# TSC_Project.net
KiCad netlist of a schematic drawn in EAGLE
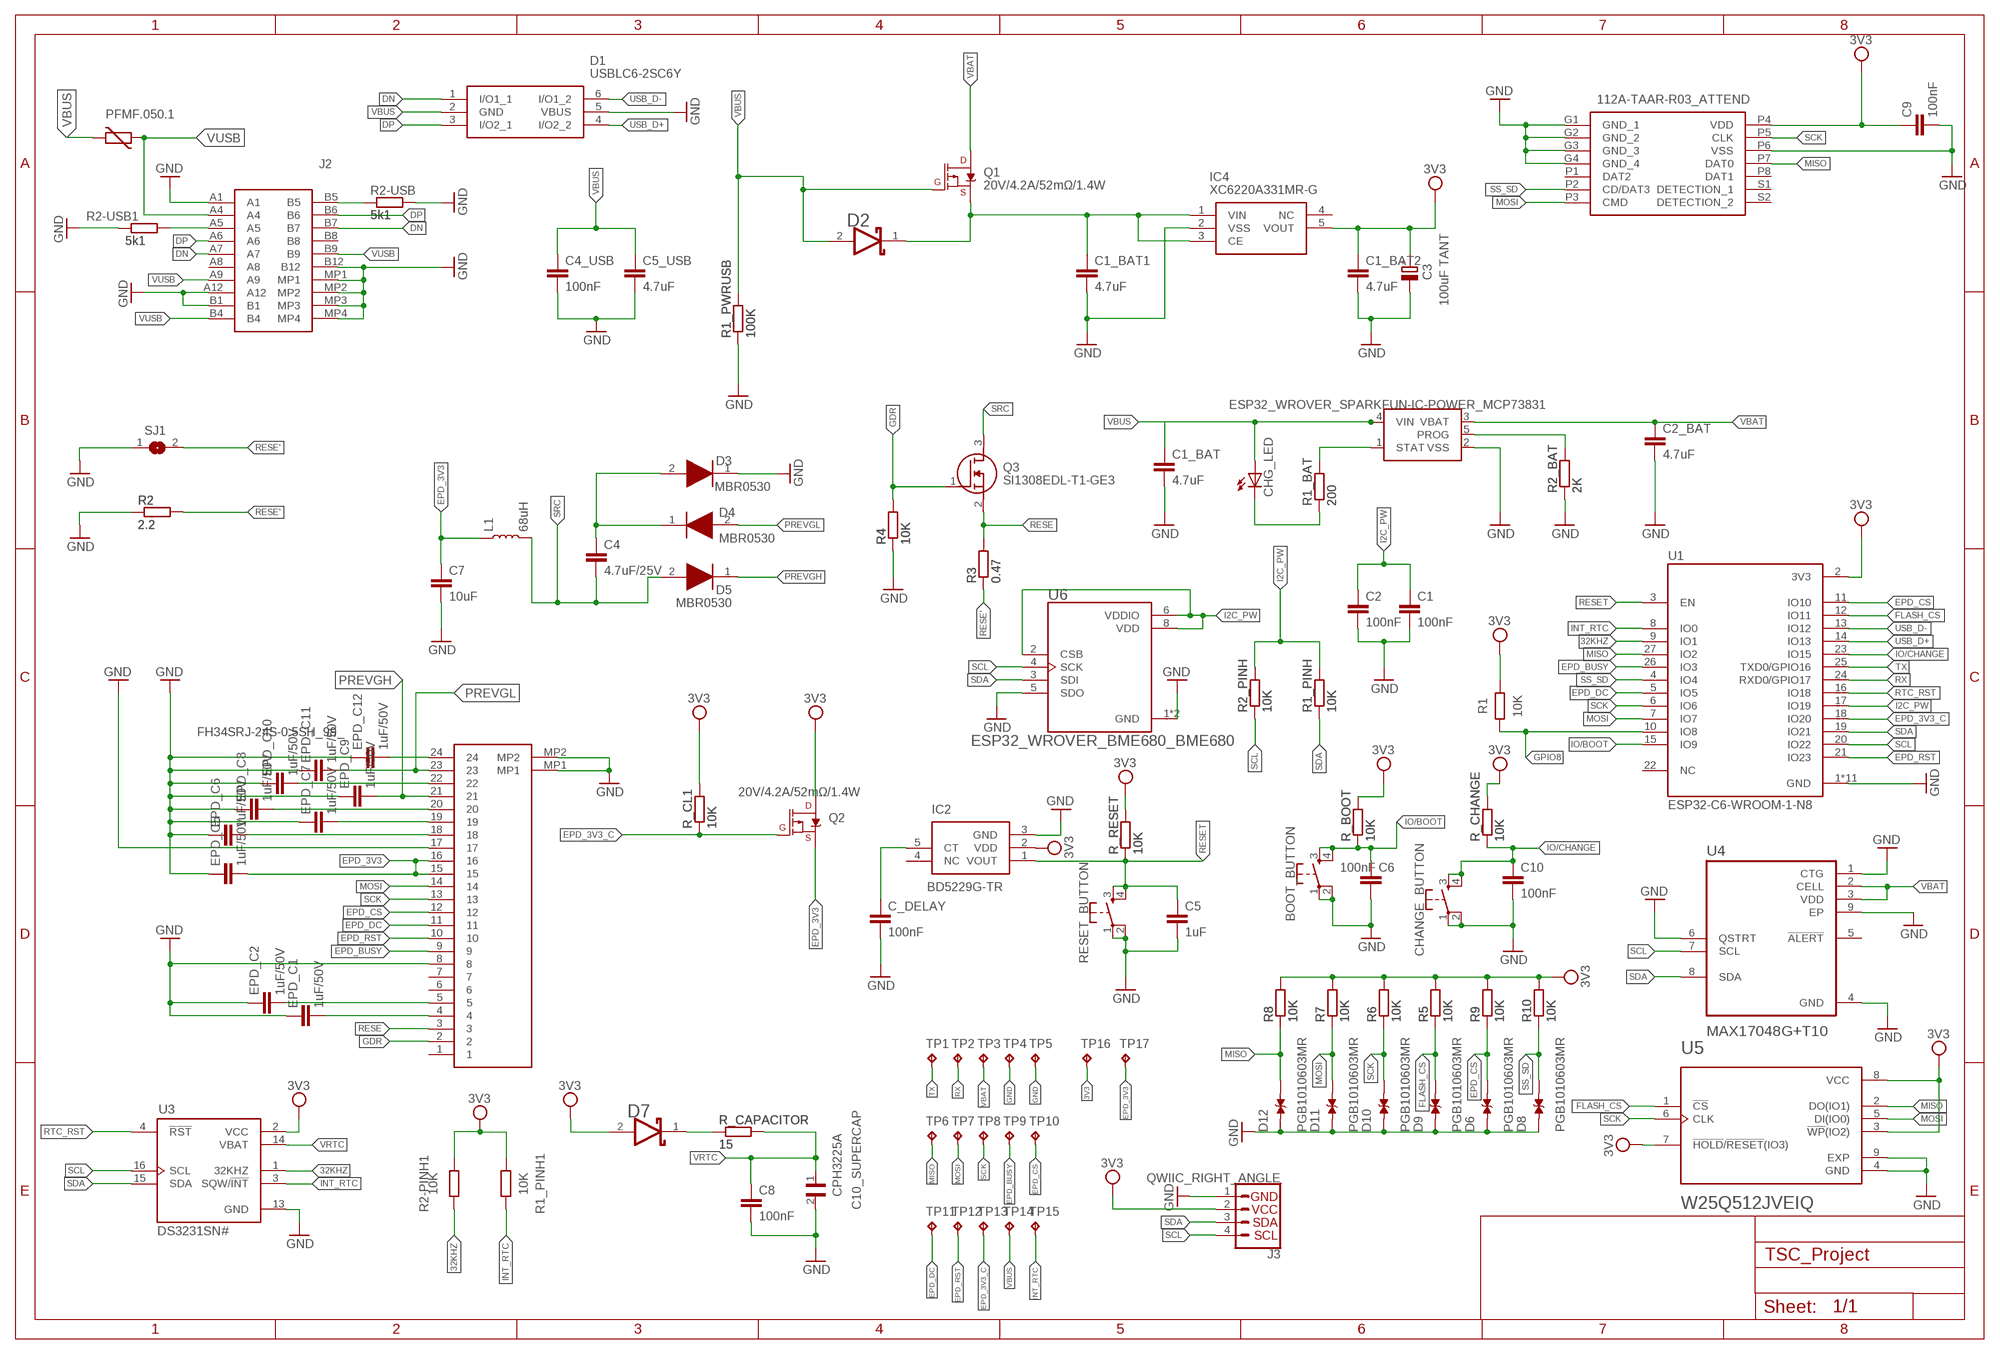
[diagram p0: schematic, sheet 1]

(export (version "E")
  (design (tool "Eeschema 10.0.6"))
  (components
    (comp (ref "BOOT_BUTTON")
      (value "BUTTON_CUSYOMV1")
      (footprint "eagle-import:MYBUTTON")
      (libsource (lib "eagle-import") (part "BUTTON_CUSYOMV1"))
    )
    (comp (ref "C1")
      (value "100nF")
      (footprint "eagle-import:ESP32_WROVER_EAGLE-LTSPICE_C0402")
      (libsource (lib "eagle-import") (part "ESP32_WROVER_EAGLE-LTSPICE_CC0402"))
    )
    (comp (ref "C1_BAT")
      (value "4.7uF")
      (footprint "eagle-import:ESP32_WROVER_EAGLE-LTSPICE_C0402")
      (libsource (lib "eagle-import") (part "ESP32_WROVER_EAGLE-LTSPICE_CC0402"))
    )
    (comp (ref "C1_BAT1")
      (value "4.7uF")
      (footprint "eagle-import:EAGLE-LTSPICE_C0402")
      (libsource (lib "eagle-import") (part "EAGLE-LTSPICE_CC0402"))
    )
    (comp (ref "C1_BAT2")
      (value "4.7uF")
      (footprint "eagle-import:EAGLE-LTSPICE_C0402")
      (libsource (lib "eagle-import") (part "EAGLE-LTSPICE_CC0402"))
    )
    (comp (ref "C2")
      (value "100nF")
      (footprint "eagle-import:ESP32_WROVER_EAGLE-LTSPICE_C0402")
      (libsource (lib "eagle-import") (part "ESP32_WROVER_EAGLE-LTSPICE_CC0402"))
    )
    (comp (ref "C2_BAT")
      (value "4.7uF")
      (footprint "eagle-import:ESP32_WROVER_EAGLE-LTSPICE_C0402")
      (libsource (lib "eagle-import") (part "ESP32_WROVER_EAGLE-LTSPICE_CC0402"))
    )
    (comp (ref "C3")
      (value "100uF TANT")
      (footprint "eagle-import:RCL_CT3528")
      (libsource (lib "eagle-import") (part "RCL_CPOL-EUCT3528"))
    )
    (comp (ref "C4")
      (value "4.7uF/25V")
      (footprint "eagle-import:ESP32_WROVER_EAGLE-LTSPICE_C0402")
      (libsource (lib "eagle-import") (part "ESP32_WROVER_EAGLE-LTSPICE_CC0402"))
    )
    (comp (ref "C4_USB")
      (value "100nF")
      (footprint "eagle-import:EAGLE-LTSPICE_C0402")
      (libsource (lib "eagle-import") (part "EAGLE-LTSPICE_CC0402"))
    )
    (comp (ref "C5")
      (value "1uF")
      (footprint "eagle-import:ESP32_WROVER_EAGLE-LTSPICE_C0402")
      (libsource (lib "eagle-import") (part "ESP32_WROVER_EAGLE-LTSPICE_CC0402"))
    )
    (comp (ref "C5_USB")
      (value "4.7uF")
      (footprint "eagle-import:EAGLE-LTSPICE_C0402")
      (libsource (lib "eagle-import") (part "EAGLE-LTSPICE_CC0402"))
    )
    (comp (ref "C6")
      (value "100nF")
      (footprint "eagle-import:ESP32_WROVER_EAGLE-LTSPICE_C0402")
      (libsource (lib "eagle-import") (part "ESP32_WROVER_EAGLE-LTSPICE_CC0402"))
    )
    (comp (ref "C7")
      (value "10uF")
      (footprint "eagle-import:ESP32_WROVER_EAGLE-LTSPICE_C0402")
      (libsource (lib "eagle-import") (part "ESP32_WROVER_EAGLE-LTSPICE_CC0402"))
    )
    (comp (ref "C8")
      (value "100nF")
      (footprint "eagle-import:ESP32_WROVER_EAGLE-LTSPICE_C0402")
      (libsource (lib "eagle-import") (part "ESP32_WROVER_EAGLE-LTSPICE_CC0402"))
    )
    (comp (ref "C9")
      (value "100nF")
      (footprint "eagle-import:ESP32_WROVER_EAGLE-LTSPICE_C0402")
      (libsource (lib "eagle-import") (part "ESP32_WROVER_EAGLE-LTSPICE_CC0402"))
    )
    (comp (ref "C10")
      (value "100nF")
      (footprint "eagle-import:ESP32_WROVER_EAGLE-LTSPICE_C0402")
      (libsource (lib "eagle-import") (part "ESP32_WROVER_EAGLE-LTSPICE_CC0402"))
    )
    (comp (ref "C10_SUPERCAP")
      (value "CPH3225A")
      (footprint "eagle-import:CAPCP3225X100N")
      (fields (field (name "MF") "Seiko Instruments"))
      (libsource (lib "eagle-import") (part "CPH3225A"))
    )
    (comp (ref "CHANGE_BUTTON")
      (value "BUTTON_CUSYOMV1")
      (footprint "eagle-import:MYBUTTON")
      (libsource (lib "eagle-import") (part "BUTTON_CUSYOMV1"))
    )
    (comp (ref "CHG_LED")
      (value "ADAFRUIT_LEDCHIP-LED0603")
      (footprint "eagle-import:ADAFRUIT_CHIP-LED0603")
      (libsource (lib "eagle-import") (part "ADAFRUIT_LEDCHIP-LED0603"))
    )
    (comp (ref "C_DELAY")
      (value "100nF")
      (footprint "eagle-import:EAGLE-LTSPICE_C0402")
      (libsource (lib "eagle-import") (part "EAGLE-LTSPICE_CC0402"))
    )
    (comp (ref "D1")
      (value "USBLC6-2SC6Y")
      (footprint "eagle-import:SOT95P280X145-6N")
      (fields (field (name "MF") "STMicroelectronics"))
      (libsource (lib "eagle-import") (part "USBLC6-2SC6Y"))
    )
    (comp (ref "D2")
      (value "ESP32_WROVER_AVX---SD0805S020S1R0_AVX_SD0805S020S1R0_0_0AVX_SD0805S020S1R0_0_0")
      (footprint "eagle-import:ESP32_WROVER_AVX---SD0805S020S1R0_AVX_SD0805S020S1R0_0")
      (fields
        (field (name "DIGIKEY_PART_NUMBER") "478-7800-1-ND")
        (field (name "MF") "AVX")
        (field (name "MOUSER_PART_NUMBER") "581-SD0805S020S1R0")
      )
      (libsource (lib "eagle-import") (part "ESP32_WROVER_AVX---SD0805S020S1R0_AVX_SD0805S020S1R0_0_0AVX_SD0805S020S1R0_0_0"))
    )
    (comp (ref "D3")
      (value "MBR0530")
      (footprint "eagle-import:SOD3716X135N")
      (fields (field (name "MF") "ON Semiconductor"))
      (libsource (lib "eagle-import") (part "MBR0530"))
    )
    (comp (ref "D4")
      (value "MBR0530")
      (footprint "eagle-import:SOD3716X135N")
      (fields (field (name "MF") "ON Semiconductor"))
      (libsource (lib "eagle-import") (part "MBR0530"))
    )
    (comp (ref "D5")
      (value "MBR0530")
      (footprint "eagle-import:SOD3716X135N")
      (fields (field (name "MF") "ON Semiconductor"))
      (libsource (lib "eagle-import") (part "MBR0530"))
    )
    (comp (ref "D6")
      (value "PGB1010603MR")
      (footprint "eagle-import:DIOC1608X36N")
      (fields (field (name "MF") "Littelfuse Inc."))
      (libsource (lib "eagle-import") (part "PGB1010603MR"))
    )
    (comp (ref "D7")
      (value "ESP32_WROVER_AVX---SD0805S020S1R0_AVX_SD0805S020S1R0_0_0AVX_SD0805S020S1R0_0_0")
      (footprint "eagle-import:ESP32_WROVER_AVX---SD0805S020S1R0_AVX_SD0805S020S1R0_0")
      (fields
        (field (name "DIGIKEY_PART_NUMBER") "478-7800-1-ND")
        (field (name "MF") "AVX")
        (field (name "MOUSER_PART_NUMBER") "581-SD0805S020S1R0")
      )
      (libsource (lib "eagle-import") (part "ESP32_WROVER_AVX---SD0805S020S1R0_AVX_SD0805S020S1R0_0_0AVX_SD0805S020S1R0_0_0"))
    )
    (comp (ref "D8")
      (value "PGB1010603MR")
      (footprint "eagle-import:DIOC1608X36N")
      (fields (field (name "MF") "Littelfuse Inc."))
      (libsource (lib "eagle-import") (part "PGB1010603MR"))
    )
    (comp (ref "D9")
      (value "PGB1010603MR")
      (footprint "eagle-import:DIOC1608X36N")
      (fields (field (name "MF") "Littelfuse Inc."))
      (libsource (lib "eagle-import") (part "PGB1010603MR"))
    )
    (comp (ref "D10")
      (value "PGB1010603MR")
      (footprint "eagle-import:DIOC1608X36N")
      (fields (field (name "MF") "Littelfuse Inc."))
      (libsource (lib "eagle-import") (part "PGB1010603MR"))
    )
    (comp (ref "D11")
      (value "PGB1010603MR")
      (footprint "eagle-import:DIOC1608X36N")
      (fields (field (name "MF") "Littelfuse Inc."))
      (libsource (lib "eagle-import") (part "PGB1010603MR"))
    )
    (comp (ref "D12")
      (value "PGB1010603MR")
      (footprint "eagle-import:DIOC1608X36N")
      (fields (field (name "MF") "Littelfuse Inc."))
      (libsource (lib "eagle-import") (part "PGB1010603MR"))
    )
    (comp (ref "EPD_C1")
      (value "1uF/50V")
      (footprint "eagle-import:ESP32_WROVER_EAGLE-LTSPICE_C0402")
      (libsource (lib "eagle-import") (part "ESP32_WROVER_EAGLE-LTSPICE_CC0402"))
    )
    (comp (ref "EPD_C2")
      (value "1uF/50V")
      (footprint "eagle-import:ESP32_WROVER_EAGLE-LTSPICE_C0402")
      (libsource (lib "eagle-import") (part "ESP32_WROVER_EAGLE-LTSPICE_CC0402"))
    )
    (comp (ref "EPD_C5")
      (value "1uF/50V")
      (footprint "eagle-import:ESP32_WROVER_EAGLE-LTSPICE_C0402")
      (libsource (lib "eagle-import") (part "ESP32_WROVER_EAGLE-LTSPICE_CC0402"))
    )
    (comp (ref "EPD_C6")
      (value "1uF/50V")
      (footprint "eagle-import:ESP32_WROVER_EAGLE-LTSPICE_C0402")
      (libsource (lib "eagle-import") (part "ESP32_WROVER_EAGLE-LTSPICE_CC0402"))
    )
    (comp (ref "EPD_C7")
      (value "1uF/50V")
      (footprint "eagle-import:ESP32_WROVER_EAGLE-LTSPICE_C0402")
      (libsource (lib "eagle-import") (part "ESP32_WROVER_EAGLE-LTSPICE_CC0402"))
    )
    (comp (ref "EPD_C8")
      (value "1uF/50V")
      (footprint "eagle-import:ESP32_WROVER_EAGLE-LTSPICE_C0402")
      (libsource (lib "eagle-import") (part "ESP32_WROVER_EAGLE-LTSPICE_CC0402"))
    )
    (comp (ref "EPD_C9")
      (value "1uF/50V")
      (footprint "eagle-import:ESP32_WROVER_EAGLE-LTSPICE_C0402")
      (libsource (lib "eagle-import") (part "ESP32_WROVER_EAGLE-LTSPICE_CC0402"))
    )
    (comp (ref "EPD_C10")
      (value "1uF/50V")
      (footprint "eagle-import:ESP32_WROVER_EAGLE-LTSPICE_C0402")
      (libsource (lib "eagle-import") (part "ESP32_WROVER_EAGLE-LTSPICE_CC0402"))
    )
    (comp (ref "EPD_C11")
      (value "1uF/50V")
      (footprint "eagle-import:ESP32_WROVER_EAGLE-LTSPICE_C0402")
      (libsource (lib "eagle-import") (part "ESP32_WROVER_EAGLE-LTSPICE_CC0402"))
    )
    (comp (ref "EPD_C12")
      (value "1uF/50V")
      (footprint "eagle-import:ESP32_WROVER_EAGLE-LTSPICE_C0402")
      (libsource (lib "eagle-import") (part "ESP32_WROVER_EAGLE-LTSPICE_CC0402"))
    )
    (comp (ref "IC2")
      (value "BD5229G-TR")
      (footprint "eagle-import:SOT95P280X125-5N")
      (fields (field (name "MOUSER_PART_NUMBER") "755-BD5229G-TR"))
      (libsource (lib "eagle-import") (part "BD5229G-TR"))
    )
    (comp (ref "IC4")
      (value "XC6220A331MR-G")
      (footprint "eagle-import:SOT95P280X120-5N")
      (fields (field (name "MOUSER_PART_NUMBER") "865-XC6220A331MR-G"))
      (libsource (lib "eagle-import") (part "XC6220A331MR-G"))
    )
    (comp (ref "J1")
      (value "FH34SRJ-24S-0.5SH_99_")
      (footprint "eagle-import:FH34SRJ24S05SH99")
      (fields
        (field (name "MANUFACTURER_PART_NUMBER") "FH34SRJ-24S-0.5SH(99)")
        (field (name "MOUSER_PART_NUMBER") "798-FH34SRJ24S05SH99")
      )
      (libsource (lib "eagle-import") (part "FH34SRJ-24S-0.5SH_99_"))
    )
    (comp (ref "J2")
      (value "SAMACSYS_PARTS_USB4110-GF-A")
      (footprint "eagle-import:SAMACSYS_PARTS_USB4110GFA")
      (fields
        (field (name "MANUFACTURER_PART_NUMBER") "USB4110-GF-A")
        (field (name "MOUSER_PART_NUMBER") "640-USB4110-GF-A")
      )
      (libsource (lib "eagle-import") (part "SAMACSYS_PARTS_USB4110-GF-A"))
    )
    (comp (ref "J3")
      (value "QWIIC_RIGHT_ANGLE")
      (footprint "eagle-import:JST04_1MM_RA")
      (libsource (lib "eagle-import") (part "QWIIC_CONNECTORJS-1MM"))
    )
    (comp (ref "J4")
      (value "112A-TAAR-R03_ATTEND")
      (footprint "eagle-import:112ATAARR03ATTEND")
      (fields (field (name "MANUFACTURER_PART_NUMBER") "112A-TAAR-R03 ATTEND"))
      (libsource (lib "eagle-import") (part "112A-TAAR-R03_ATTEND"))
    )
    (comp (ref "L1")
      (value "68uH")
      (footprint "eagle-import:CR75")
      (libsource (lib "eagle-import") (part "INDUCTOR-CR75-68UH"))
    )
    (comp (ref "PFMF.050.1")
      (value "ESP32C6_VARISTORCN1812")
      (footprint "eagle-import:ESP32C6_VARISTOR_CT_CN1812")
      (libsource (lib "eagle-import") (part "ESP32C6_VARISTORCN1812"))
    )
    (comp (ref "Q1")
      (value "20V/4.2A/52mΩ/1.4W")
      (footprint "eagle-import:ESP32_WROVER_SPARKFUN-DISCRETESEMI_SOT23-3")
      (libsource (lib "eagle-import") (part "ESP32_WROVER_SPARKFUN-DISCRETESEMI_MOSFET_PCH-DMG2305UX-7"))
    )
    (comp (ref "Q2")
      (value "20V/4.2A/52mΩ/1.4W")
      (footprint "eagle-import:ESP32_WROVER_SPARKFUN-DISCRETESEMI_SOT23-3")
      (libsource (lib "eagle-import") (part "ESP32_WROVER_SPARKFUN-DISCRETESEMI_MOSFET_PCH-DMG2305UX-7"))
    )
    (comp (ref "Q3")
      (value "SI1308EDL-T1-GE3")
      (footprint "eagle-import:SOT65P210X110-3N")
      (fields (field (name "MF") "Vishay Siliconix"))
      (libsource (lib "eagle-import") (part "SI1308EDL-T1-GE3"))
    )
    (comp (ref "R1")
      (value "10K")
      (footprint "eagle-import:ESP32_WROVER_EAGLE-LTSPICE_R0402")
      (libsource (lib "eagle-import") (part "ESP32_WROVER_EAGLE-LTSPICE_RR0402"))
    )
    (comp (ref "R1_BAT")
      (value "200")
      (footprint "eagle-import:ESP32_WROVER_EAGLE-LTSPICE_R0402")
      (libsource (lib "eagle-import") (part "ESP32_WROVER_EAGLE-LTSPICE_RR0402"))
    )
    (comp (ref "R1_PINH")
      (value "10K")
      (footprint "eagle-import:ESP32_WROVER_EAGLE-LTSPICE_R0402")
      (libsource (lib "eagle-import") (part "ESP32_WROVER_EAGLE-LTSPICE_RR0402"))
    )
    (comp (ref "R1_PINH1")
      (value "10K")
      (footprint "eagle-import:ESP32_WROVER_EAGLE-LTSPICE_R0402")
      (libsource (lib "eagle-import") (part "ESP32_WROVER_EAGLE-LTSPICE_RR0402"))
    )
    (comp (ref "R1_PWRUSB")
      (value "100K")
      (footprint "eagle-import:ESP32_WROVER_EAGLE-LTSPICE_R0402")
      (libsource (lib "eagle-import") (part "ESP32_WROVER_EAGLE-LTSPICE_RR0402"))
    )
    (comp (ref "R2")
      (value "2.2")
      (footprint "eagle-import:ESP32_WROVER_EAGLE-LTSPICE_R0402")
      (libsource (lib "eagle-import") (part "ESP32_WROVER_EAGLE-LTSPICE_RR0402"))
    )
    (comp (ref "R2-PINH1")
      (value "10K")
      (footprint "eagle-import:ESP32_WROVER_EAGLE-LTSPICE_R0402")
      (libsource (lib "eagle-import") (part "ESP32_WROVER_EAGLE-LTSPICE_RR0402"))
    )
    (comp (ref "R2-USB")
      (value "5k1")
      (footprint "eagle-import:ESP32_WROVER_EAGLE-LTSPICE_R0402")
      (libsource (lib "eagle-import") (part "ESP32_WROVER_EAGLE-LTSPICE_RR0402"))
    )
    (comp (ref "R2-USB1")
      (value "5k1")
      (footprint "eagle-import:ESP32_WROVER_EAGLE-LTSPICE_R0402")
      (libsource (lib "eagle-import") (part "ESP32_WROVER_EAGLE-LTSPICE_RR0402"))
    )
    (comp (ref "R2_BAT")
      (value "2K")
      (footprint "eagle-import:ESP32_WROVER_EAGLE-LTSPICE_R0402")
      (libsource (lib "eagle-import") (part "ESP32_WROVER_EAGLE-LTSPICE_RR0402"))
    )
    (comp (ref "R2_PINH")
      (value "10K")
      (footprint "eagle-import:ESP32_WROVER_EAGLE-LTSPICE_R0402")
      (libsource (lib "eagle-import") (part "ESP32_WROVER_EAGLE-LTSPICE_RR0402"))
    )
    (comp (ref "R3")
      (value "0.47")
      (footprint "eagle-import:ESP32_WROVER_EAGLE-LTSPICE_R0402")
      (libsource (lib "eagle-import") (part "ESP32_WROVER_EAGLE-LTSPICE_RR0402"))
    )
    (comp (ref "R4")
      (value "10K")
      (footprint "eagle-import:ESP32_WROVER_EAGLE-LTSPICE_R0402")
      (libsource (lib "eagle-import") (part "ESP32_WROVER_EAGLE-LTSPICE_RR0402"))
    )
    (comp (ref "R5")
      (value "10K")
      (footprint "eagle-import:ESP32_WROVER_EAGLE-LTSPICE_R0402")
      (libsource (lib "eagle-import") (part "ESP32_WROVER_EAGLE-LTSPICE_RR0402"))
    )
    (comp (ref "R6")
      (value "10K")
      (footprint "eagle-import:ESP32_WROVER_EAGLE-LTSPICE_R0402")
      (libsource (lib "eagle-import") (part "ESP32_WROVER_EAGLE-LTSPICE_RR0402"))
    )
    (comp (ref "R7")
      (value "10K")
      (footprint "eagle-import:ESP32_WROVER_EAGLE-LTSPICE_R0402")
      (libsource (lib "eagle-import") (part "ESP32_WROVER_EAGLE-LTSPICE_RR0402"))
    )
    (comp (ref "R8")
      (value "10K")
      (footprint "eagle-import:ESP32_WROVER_EAGLE-LTSPICE_R0402")
      (libsource (lib "eagle-import") (part "ESP32_WROVER_EAGLE-LTSPICE_RR0402"))
    )
    (comp (ref "R9")
      (value "10K")
      (footprint "eagle-import:ESP32_WROVER_EAGLE-LTSPICE_R0402")
      (libsource (lib "eagle-import") (part "ESP32_WROVER_EAGLE-LTSPICE_RR0402"))
    )
    (comp (ref "R10")
      (value "10K")
      (footprint "eagle-import:ESP32_WROVER_EAGLE-LTSPICE_R0402")
      (libsource (lib "eagle-import") (part "ESP32_WROVER_EAGLE-LTSPICE_RR0402"))
    )
    (comp (ref "RESET_BUTTON")
      (value "BUTTON_CUSYOMV1")
      (footprint "eagle-import:MYBUTTON")
      (libsource (lib "eagle-import") (part "BUTTON_CUSYOMV1"))
    )
    (comp (ref "R_BOOT")
      (value "10K")
      (footprint "eagle-import:ESP32_WROVER_EAGLE-LTSPICE_R0402")
      (libsource (lib "eagle-import") (part "ESP32_WROVER_EAGLE-LTSPICE_RR0402"))
    )
    (comp (ref "R_CAPACITOR")
      (value "15")
      (footprint "eagle-import:ESP32_WROVER_EAGLE-LTSPICE_R0402")
      (libsource (lib "eagle-import") (part "ESP32_WROVER_EAGLE-LTSPICE_RR0402"))
    )
    (comp (ref "R_CHANGE")
      (value "10K")
      (footprint "eagle-import:ESP32_WROVER_EAGLE-LTSPICE_R0402")
      (libsource (lib "eagle-import") (part "ESP32_WROVER_EAGLE-LTSPICE_RR0402"))
    )
    (comp (ref "R_CL1")
      (value "10K")
      (footprint "eagle-import:ESP32_WROVER_EAGLE-LTSPICE_R0402")
      (libsource (lib "eagle-import") (part "ESP32_WROVER_EAGLE-LTSPICE_RR0402"))
    )
    (comp (ref "R_RESET")
      (value "10K")
      (footprint "eagle-import:ESP32_WROVER_EAGLE-LTSPICE_R0402")
      (libsource (lib "eagle-import") (part "ESP32_WROVER_EAGLE-LTSPICE_RR0402"))
    )
    (comp (ref "SJ1") (value "SJ") (footprint "eagle-import:SJ") (libsource (lib "eagle-import") (part "SJ")))
    (comp (ref "TP1")
      (value "TPTP20R")
      (footprint "eagle-import:TP20R")
      (libsource (lib "eagle-import") (part "TPTP20R"))
    )
    (comp (ref "TP2")
      (value "TPTP20R")
      (footprint "eagle-import:TP20R")
      (libsource (lib "eagle-import") (part "TPTP20R"))
    )
    (comp (ref "TP3")
      (value "TPTP20R")
      (footprint "eagle-import:TP20R")
      (libsource (lib "eagle-import") (part "TPTP20R"))
    )
    (comp (ref "TP4")
      (value "TPTP20R")
      (footprint "eagle-import:TP20R")
      (libsource (lib "eagle-import") (part "TPTP20R"))
    )
    (comp (ref "TP5")
      (value "TPTP20R")
      (footprint "eagle-import:TP20R")
      (libsource (lib "eagle-import") (part "TPTP20R"))
    )
    (comp (ref "TP6")
      (value "TPTP20R")
      (footprint "eagle-import:TP20R")
      (libsource (lib "eagle-import") (part "TPTP20R"))
    )
    (comp (ref "TP7")
      (value "TPTP20R")
      (footprint "eagle-import:TP20R")
      (libsource (lib "eagle-import") (part "TPTP20R"))
    )
    (comp (ref "TP8")
      (value "TPTP20R")
      (footprint "eagle-import:TP20R")
      (libsource (lib "eagle-import") (part "TPTP20R"))
    )
    (comp (ref "TP9")
      (value "TPTP20R")
      (footprint "eagle-import:TP20R")
      (libsource (lib "eagle-import") (part "TPTP20R"))
    )
    (comp (ref "TP10")
      (value "TPTP20R")
      (footprint "eagle-import:TP20R")
      (libsource (lib "eagle-import") (part "TPTP20R"))
    )
    (comp (ref "TP11")
      (value "TPTP20R")
      (footprint "eagle-import:TP20R")
      (libsource (lib "eagle-import") (part "TPTP20R"))
    )
    (comp (ref "TP12")
      (value "TPTP20R")
      (footprint "eagle-import:TP20R")
      (libsource (lib "eagle-import") (part "TPTP20R"))
    )
    (comp (ref "TP13")
      (value "TPTP20R")
      (footprint "eagle-import:TP20R")
      (libsource (lib "eagle-import") (part "TPTP20R"))
    )
    (comp (ref "TP14")
      (value "TPTP20R")
      (footprint "eagle-import:TP20R")
      (libsource (lib "eagle-import") (part "TPTP20R"))
    )
    (comp (ref "TP15")
      (value "TPTP20R")
      (footprint "eagle-import:TP20R")
      (libsource (lib "eagle-import") (part "TPTP20R"))
    )
    (comp (ref "TP16")
      (value "TPTP20R")
      (footprint "eagle-import:TP20R")
      (libsource (lib "eagle-import") (part "TPTP20R"))
    )
    (comp (ref "TP17")
      (value "TPTP20R")
      (footprint "eagle-import:TP20R")
      (libsource (lib "eagle-import") (part "TPTP20R"))
    )
    (comp (ref "U1")
      (value "ESP32-C6-WROOM-1-N8")
      (footprint "eagle-import:XCVR_ESP32-C6-WROOM-1-N8")
      (fields (field (name "MF") "Espressif Systems"))
      (libsource (lib "eagle-import") (part "ESP32-C6-WROOM-1-N8"))
    )
    (comp (ref "U2")
      (value "ESP32_WROVER_SPARKFUN-IC-POWER_MCP73831")
      (footprint "eagle-import:ESP32_WROVER_SPARKFUN-IC-POWER_SOT23-5")
      (libsource (lib "eagle-import") (part "ESP32_WROVER_SPARKFUN-IC-POWER_MCP73831"))
    )
    (comp (ref "U3")
      (value "DS3231SN#")
      (footprint "eagle-import:SOIC127P1032X265-16N")
      (fields (field (name "MF") "Analog Devices"))
      (libsource (lib "eagle-import") (part "DS3231SN#"))
    )
    (comp (ref "U4")
      (value "MAX17048G+T10")
      (footprint "eagle-import:SON50P200X200X80-9N")
      (fields (field (name "MF") "Analog Devices"))
      (libsource (lib "eagle-import") (part "MAX17048G+T10"))
    )
    (comp (ref "U5")
      (value "W25Q512JVEIQ")
      (footprint "eagle-import:SON127P600X800X80-9N")
      (fields (field (name "MF") "Winbond Electronics"))
      (libsource (lib "eagle-import") (part "W25Q512JVEIQ"))
    )
    (comp (ref "U6")
      (value "ESP32_WROVER_BME680_BME680")
      (footprint "eagle-import:ESP32_WROVER_BME680_PSON80P300X300X100-8N")
      (fields (field (name "MF") "Bosch Sensortec") (field (name "MP") "BME680"))
      (libsource (lib "eagle-import") (part "ESP32_WROVER_BME680_BME680"))
    )
  )
  (nets
    (net (code "1") (name "3V3") (class "Default")
      (node (ref "C1_BAT2") (pin "1") (pinfunction "1_1") (pintype "passive"))
      (node (ref "C3") (pin "+") (pinfunction "+_+") (pintype "passive"))
      (node (ref "C9") (pin "1") (pinfunction "1_1") (pintype "passive"))
      (node (ref "D7") (pin "2") (pinfunction "ANODE_2") (pintype "bidirectional"))
      (node (ref "IC2") (pin "2") (pinfunction "VDD_2") (pintype "bidirectional"))
      (node (ref "IC4") (pin "5") (pinfunction "VOUT_5") (pintype "bidirectional"))
      (node (ref "J3") (pin "2") (pinfunction "2_2") (pintype "power_in"))
      (node (ref "J4") (pin "P4") (pinfunction "VDD_P4") (pintype "bidirectional"))
      (node (ref "Q2") (pin "3") (pinfunction "D_3") (pintype "bidirectional"))
      (node (ref "R1") (pin "2") (pinfunction "2_2") (pintype "passive"))
      (node (ref "R10") (pin "2") (pinfunction "2_2") (pintype "passive"))
      (node (ref "R1_PINH1") (pin "2") (pinfunction "2_2") (pintype "passive"))
      (node (ref "R2-PINH1") (pin "2") (pinfunction "2_2") (pintype "passive"))
      (node (ref "R5") (pin "2") (pinfunction "2_2") (pintype "passive"))
      (node (ref "R6") (pin "2") (pinfunction "2_2") (pintype "passive"))
      (node (ref "R7") (pin "2") (pinfunction "2_2") (pintype "passive"))
      (node (ref "R8") (pin "2") (pinfunction "2_2") (pintype "passive"))
      (node (ref "R9") (pin "2") (pinfunction "2_2") (pintype "passive"))
      (node (ref "R_BOOT") (pin "2") (pinfunction "2_2") (pintype "passive"))
      (node (ref "R_CHANGE") (pin "2") (pinfunction "2_2") (pintype "passive"))
      (node (ref "R_CL1") (pin "2") (pinfunction "2_2") (pintype "passive"))
      (node (ref "R_RESET") (pin "2") (pinfunction "2_2") (pintype "passive"))
      (node (ref "TP16") (pin "TP") (pinfunction "TP_TP") (pintype "input"))
      (node (ref "U1") (pin "2") (pinfunction "3V3_2") (pintype "power_in"))
      (node (ref "U3") (pin "2") (pinfunction "VCC_2") (pintype "power_in"))
      (node (ref "U5") (pin "3") (pinfunction "~{WP}(IO2)_3") (pintype "bidirectional"))
      (node (ref "U5") (pin "7") (pinfunction "~{HOLD}/~{RESET}(IO3)_7") (pintype "bidirectional"))
      (node (ref "U5") (pin "8") (pinfunction "VCC_8") (pintype "power_in"))
    )
    (net (code "2") (name "32KHZ") (class "Default")
      (node (ref "R2-PINH1") (pin "1") (pinfunction "1_1") (pintype "passive"))
      (node (ref "U1") (pin "9") (pinfunction "IO1_9") (pintype "bidirectional"))
      (node (ref "U3") (pin "1") (pinfunction "32KHZ_1") (pintype "output"))
    )
    (net (code "3") (name "DN") (class "Default")
      (node (ref "D1") (pin "1") (pinfunction "I/O1_1_1") (pintype "bidirectional"))
      (node (ref "J2") (pin "A7") (pinfunction "A7_A7") (pintype "bidirectional"))
      (node (ref "J2") (pin "B7") (pinfunction "B7_B7") (pintype "bidirectional"))
    )
    (net (code "4") (name "DP") (class "Default")
      (node (ref "D1") (pin "3") (pinfunction "I/O2_1_3") (pintype "bidirectional"))
      (node (ref "J2") (pin "A6") (pinfunction "A6_A6") (pintype "bidirectional"))
      (node (ref "J2") (pin "B6") (pinfunction "B6_B6") (pintype "bidirectional"))
    )
    (net (code "5") (name "EPD_3V3") (class "Default")
      (node (ref "C7") (pin "1") (pinfunction "1_1") (pintype "passive"))
      (node (ref "EPD_C5") (pin "2") (pinfunction "2_2") (pintype "passive"))
      (node (ref "J1") (pin "15") (pinfunction "15_15") (pintype "bidirectional"))
      (node (ref "J1") (pin "16") (pinfunction "16_16") (pintype "bidirectional"))
      (node (ref "L1") (pin "P$1") (pinfunction "1_P$1") (pintype "passive"))
      (node (ref "Q2") (pin "2") (pinfunction "S_2") (pintype "bidirectional"))
      (node (ref "TP17") (pin "TP") (pinfunction "TP_TP") (pintype "input"))
    )
    (net (code "6") (name "EPD_3V3_C") (class "Default")
      (node (ref "Q2") (pin "1") (pinfunction "G_1") (pintype "bidirectional"))
      (node (ref "R_CL1") (pin "1") (pinfunction "1_1") (pintype "passive"))
      (node (ref "TP13") (pin "TP") (pinfunction "TP_TP") (pintype "input"))
      (node (ref "U1") (pin "18") (pinfunction "IO20_18") (pintype "bidirectional"))
    )
    (net (code "7") (name "EPD_BUSY") (class "Default")
      (node (ref "J1") (pin "9") (pinfunction "9_9") (pintype "bidirectional"))
      (node (ref "TP9") (pin "TP") (pinfunction "TP_TP") (pintype "input"))
      (node (ref "U1") (pin "26") (pinfunction "IO3_26") (pintype "bidirectional"))
    )
    (net (code "8") (name "EPD_CS") (class "Default")
      (node (ref "D6") (pin "2") (pinfunction "2_2") (pintype "passive"))
      (node (ref "J1") (pin "12") (pinfunction "12_12") (pintype "bidirectional"))
      (node (ref "R9") (pin "1") (pinfunction "1_1") (pintype "passive"))
      (node (ref "TP10") (pin "TP") (pinfunction "TP_TP") (pintype "input"))
      (node (ref "U1") (pin "11") (pinfunction "IO10_11") (pintype "bidirectional"))
    )
    (net (code "9") (name "EPD_DC") (class "Default")
      (node (ref "J1") (pin "11") (pinfunction "11_11") (pintype "bidirectional"))
      (node (ref "TP11") (pin "TP") (pinfunction "TP_TP") (pintype "input"))
      (node (ref "U1") (pin "5") (pinfunction "IO5_5") (pintype "bidirectional"))
    )
    (net (code "10") (name "EPD_RST") (class "Default")
      (node (ref "J1") (pin "10") (pinfunction "10_10") (pintype "bidirectional"))
      (node (ref "TP12") (pin "TP") (pinfunction "TP_TP") (pintype "input"))
      (node (ref "U1") (pin "21") (pinfunction "IO23_21") (pintype "bidirectional"))
    )
    (net (code "11") (name "FLASH_CS") (class "Default")
      (node (ref "D9") (pin "2") (pinfunction "2_2") (pintype "passive"))
      (node (ref "R5") (pin "1") (pinfunction "1_1") (pintype "passive"))
      (node (ref "U1") (pin "12") (pinfunction "IO11_12") (pintype "bidirectional"))
      (node (ref "U5") (pin "1") (pinfunction "~{CS}_1") (pintype "input"))
    )
    (net (code "12") (name "GDR") (class "Default")
      (node (ref "J1") (pin "2") (pinfunction "2_2") (pintype "bidirectional"))
      (node (ref "Q3") (pin "1") (pinfunction "G_1") (pintype "bidirectional"))
      (node (ref "R4") (pin "2") (pinfunction "2_2") (pintype "passive"))
    )
    (net (code "13") (name "GND") (class "Default")
      (node (ref "BOOT_BUTTON") (pin "1") (pinfunction "1_1") (pintype "passive"))
      (node (ref "BOOT_BUTTON") (pin "2") (pinfunction "2_2") (pintype "passive"))
      (node (ref "C1") (pin "2") (pinfunction "2_2") (pintype "passive"))
      (node (ref "C10") (pin "2") (pinfunction "2_2") (pintype "passive"))
      (node (ref "C10_SUPERCAP") (pin "2") (pinfunction "2_2") (pintype "passive"))
      (node (ref "C1_BAT") (pin "2") (pinfunction "2_2") (pintype "passive"))
      (node (ref "C1_BAT1") (pin "2") (pinfunction "2_2") (pintype "passive"))
      (node (ref "C1_BAT2") (pin "2") (pinfunction "2_2") (pintype "passive"))
      (node (ref "C2") (pin "2") (pinfunction "2_2") (pintype "passive"))
      (node (ref "C2_BAT") (pin "2") (pinfunction "2_2") (pintype "passive"))
      (node (ref "C3") (pin "-") (pinfunction "-_-") (pintype "passive"))
      (node (ref "C4_USB") (pin "2") (pinfunction "2_2") (pintype "passive"))
      (node (ref "C5") (pin "2") (pinfunction "2_2") (pintype "passive"))
      (node (ref "C5_USB") (pin "2") (pinfunction "2_2") (pintype "passive"))
      (node (ref "C6") (pin "2") (pinfunction "2_2") (pintype "passive"))
      (node (ref "C7") (pin "2") (pinfunction "2_2") (pintype "passive"))
      (node (ref "C8") (pin "2") (pinfunction "2_2") (pintype "passive"))
      (node (ref "C9") (pin "2") (pinfunction "2_2") (pintype "passive"))
      (node (ref "CHANGE_BUTTON") (pin "1") (pinfunction "1_1") (pintype "passive"))
      (node (ref "CHANGE_BUTTON") (pin "2") (pinfunction "2_2") (pintype "passive"))
      (node (ref "C_DELAY") (pin "2") (pinfunction "2_2") (pintype "passive"))
      (node (ref "D1") (pin "5") (pinfunction "VBUS_5") (pintype "bidirectional"))
      (node (ref "D10") (pin "1") (pinfunction "1_1") (pintype "passive"))
      (node (ref "D11") (pin "1") (pinfunction "1_1") (pintype "passive"))
      (node (ref "D12") (pin "1") (pinfunction "1_1") (pintype "passive"))
      (node (ref "D3") (pin "1") (pinfunction "K_1") (pintype "bidirectional"))
      (node (ref "D6") (pin "1") (pinfunction "1_1") (pintype "passive"))
      (node (ref "D8") (pin "1") (pinfunction "1_1") (pintype "passive"))
      (node (ref "D9") (pin "1") (pinfunction "1_1") (pintype "passive"))
      (node (ref "EPD_C1") (pin "1") (pinfunction "1_1") (pintype "passive"))
      (node (ref "EPD_C10") (pin "1") (pinfunction "1_1") (pintype "passive"))
      (node (ref "EPD_C11") (pin "1") (pinfunction "1_1") (pintype "passive"))
      (node (ref "EPD_C12") (pin "1") (pinfunction "1_1") (pintype "passive"))
      (node (ref "EPD_C2") (pin "1") (pinfunction "1_1") (pintype "passive"))
      (node (ref "EPD_C5") (pin "1") (pinfunction "1_1") (pintype "passive"))
      (node (ref "EPD_C6") (pin "1") (pinfunction "1_1") (pintype "passive"))
      (node (ref "EPD_C7") (pin "1") (pinfunction "1_1") (pintype "passive"))
      (node (ref "EPD_C8") (pin "1") (pinfunction "1_1") (pintype "passive"))
      (node (ref "EPD_C9") (pin "1") (pinfunction "1_1") (pintype "passive"))
      (node (ref "IC2") (pin "3") (pinfunction "GND_3") (pintype "bidirectional"))
      (node (ref "IC4") (pin "2") (pinfunction "VSS_2") (pintype "bidirectional"))
      (node (ref "J1") (pin "17") (pinfunction "17_17") (pintype "bidirectional"))
      (node (ref "J1") (pin "8") (pinfunction "8_8") (pintype "bidirectional"))
      (node (ref "J1") (pin "MP1") (pinfunction "MP1_MP1") (pintype "bidirectional"))
      (node (ref "J1") (pin "MP2") (pinfunction "MP2_MP2") (pintype "bidirectional"))
      (node (ref "J2") (pin "A1") (pinfunction "A1_A1") (pintype "bidirectional"))
      (node (ref "J2") (pin "A12") (pinfunction "A12_A12") (pintype "bidirectional"))
      (node (ref "J2") (pin "B1") (pinfunction "B1_B1") (pintype "bidirectional"))
      (node (ref "J2") (pin "B12") (pinfunction "B12_B12") (pintype "bidirectional"))
      (node (ref "J2") (pin "MP1") (pinfunction "MP1_MP1") (pintype "bidirectional"))
      (node (ref "J2") (pin "MP2") (pinfunction "MP2_MP2") (pintype "bidirectional"))
      (node (ref "J2") (pin "MP3") (pinfunction "MP3_MP3") (pintype "bidirectional"))
      (node (ref "J2") (pin "MP4") (pinfunction "MP4_MP4") (pintype "bidirectional"))
      (node (ref "J3") (pin "1") (pinfunction "1_1") (pintype "power_in"))
      (node (ref "J4") (pin "G1") (pinfunction "GND_1_G1") (pintype "bidirectional"))
      (node (ref "J4") (pin "G2") (pinfunction "GND_2_G2") (pintype "bidirectional"))
      (node (ref "J4") (pin "G3") (pinfunction "GND_3_G3") (pintype "bidirectional"))
      (node (ref "J4") (pin "G4") (pinfunction "GND_4_G4") (pintype "bidirectional"))
      (node (ref "J4") (pin "P6") (pinfunction "VSS_P6") (pintype "bidirectional"))
      (node (ref "R1_PWRUSB") (pin "1") (pinfunction "1_1") (pintype "passive"))
      (node (ref "R2") (pin "1") (pinfunction "1_1") (pintype "passive"))
      (node (ref "R2-USB") (pin "2") (pinfunction "2_2") (pintype "passive"))
      (node (ref "R2-USB1") (pin "1") (pinfunction "1_1") (pintype "passive"))
      (node (ref "R2_BAT") (pin "1") (pinfunction "1_1") (pintype "passive"))
      (node (ref "R4") (pin "1") (pinfunction "1_1") (pintype "passive"))
      (node (ref "RESET_BUTTON") (pin "1") (pinfunction "1_1") (pintype "passive"))
      (node (ref "RESET_BUTTON") (pin "2") (pinfunction "2_2") (pintype "passive"))
      (node (ref "SJ1") (pin "1") (pinfunction "1_1") (pintype "passive"))
      (node (ref "TP4") (pin "TP") (pinfunction "TP_TP") (pintype "input"))
      (node (ref "TP5") (pin "TP") (pinfunction "TP_TP") (pintype "input"))
      (node (ref "U1") (pin "1") (pinfunction "GND_1") (pintype "power_in"))
      (node (ref "U1") (pin "28") (pinfunction "GND_28") (pintype "power_in"))
      (node (ref "U1") (pin "29_1") (pinfunction "GND_29_1") (pintype "power_in"))
      (node (ref "U1") (pin "29_2") (pinfunction "GND_29_2") (pintype "power_in"))
      (node (ref "U1") (pin "29_3") (pinfunction "GND_29_3") (pintype "power_in"))
      (node (ref "U1") (pin "29_4") (pinfunction "GND_29_4") (pintype "power_in"))
      (node (ref "U1") (pin "29_5") (pinfunction "GND_29_5") (pintype "power_in"))
      (node (ref "U1") (pin "29_6") (pinfunction "GND_29_6") (pintype "power_in"))
      (node (ref "U1") (pin "29_7") (pinfunction "GND_29_7") (pintype "power_in"))
      (node (ref "U1") (pin "29_8") (pinfunction "GND_29_8") (pintype "power_in"))
      (node (ref "U1") (pin "29_9") (pinfunction "GND_29_9") (pintype "power_in"))
      (node (ref "U2") (pin "2") (pinfunction "VSS_2") (pintype "power_in"))
      (node (ref "U3") (pin "13") (pinfunction "GND_13") (pintype "power_in"))
      (node (ref "U4") (pin "1") (pinfunction "CTG_1") (pintype "power_in"))
      (node (ref "U4") (pin "4") (pinfunction "GND_4") (pintype "power_in"))
      (node (ref "U4") (pin "6") (pinfunction "QSTRT_6") (pintype "input"))
      (node (ref "U4") (pin "9") (pinfunction "EP_9") (pintype "power_in"))
      (node (ref "U5") (pin "4") (pinfunction "GND_4") (pintype "power_in"))
      (node (ref "U5") (pin "9") (pinfunction "EXP_9") (pintype "passive"))
      (node (ref "U6") (pin "1") (pinfunction "GND_1") (pintype "power_in"))
      (node (ref "U6") (pin "5") (pinfunction "SDO_5") (pintype "bidirectional"))
      (node (ref "U6") (pin "7") (pinfunction "GND_7") (pintype "power_in"))
    )
    (net (code "14") (name "GPIO8") (class "Default")
      (node (ref "R1") (pin "1") (pinfunction "1_1") (pintype "passive"))
      (node (ref "U1") (pin "10") (pinfunction "IO8_10") (pintype "bidirectional"))
    )
    (net (code "15") (name "I2C_PW") (class "Default")
      (node (ref "C1") (pin "1") (pinfunction "1_1") (pintype "passive"))
      (node (ref "C2") (pin "1") (pinfunction "1_1") (pintype "passive"))
      (node (ref "R1_PINH") (pin "2") (pinfunction "2_2") (pintype "passive"))
      (node (ref "R2_PINH") (pin "2") (pinfunction "2_2") (pintype "passive"))
      (node (ref "U1") (pin "17") (pinfunction "IO19_17") (pintype "bidirectional"))
      (node (ref "U6") (pin "2") (pinfunction "CSB_2") (pintype "input"))
      (node (ref "U6") (pin "6") (pinfunction "VDDIO_6") (pintype "power_in"))
      (node (ref "U6") (pin "8") (pinfunction "VDD_8") (pintype "power_in"))
    )
    (net (code "16") (name "INT_RTC") (class "Default")
      (node (ref "R1_PINH1") (pin "1") (pinfunction "1_1") (pintype "passive"))
      (node (ref "TP15") (pin "TP") (pinfunction "TP_TP") (pintype "input"))
      (node (ref "U1") (pin "8") (pinfunction "IO0_8") (pintype "bidirectional"))
      (node (ref "U3") (pin "3") (pinfunction "SQW/~{INT}_3") (pintype "output"))
    )
    (net (code "17") (name "IO{slash}BOOT") (class "Default")
      (node (ref "BOOT_BUTTON") (pin "3") (pinfunction "3_3") (pintype "passive"))
      (node (ref "BOOT_BUTTON") (pin "4") (pinfunction "4_4") (pintype "passive"))
      (node (ref "C6") (pin "1") (pinfunction "1_1") (pintype "passive"))
      (node (ref "R_BOOT") (pin "1") (pinfunction "1_1") (pintype "passive"))
      (node (ref "U1") (pin "15") (pinfunction "IO9_15") (pintype "bidirectional"))
    )
    (net (code "18") (name "IO{slash}CHANGE") (class "Default")
      (node (ref "C10") (pin "1") (pinfunction "1_1") (pintype "passive"))
      (node (ref "CHANGE_BUTTON") (pin "3") (pinfunction "3_3") (pintype "passive"))
      (node (ref "CHANGE_BUTTON") (pin "4") (pinfunction "4_4") (pintype "passive"))
      (node (ref "R_CHANGE") (pin "1") (pinfunction "1_1") (pintype "passive"))
      (node (ref "U1") (pin "23") (pinfunction "IO15_23") (pintype "bidirectional"))
    )
    (net (code "19") (name "MISO") (class "Default")
      (node (ref "D12") (pin "2") (pinfunction "2_2") (pintype "passive"))
      (node (ref "J4") (pin "P7") (pinfunction "DAT0_P7") (pintype "bidirectional"))
      (node (ref "R8") (pin "1") (pinfunction "1_1") (pintype "passive"))
      (node (ref "TP6") (pin "TP") (pinfunction "TP_TP") (pintype "input"))
      (node (ref "U1") (pin "27") (pinfunction "IO2_27") (pintype "bidirectional"))
      (node (ref "U5") (pin "2") (pinfunction "DO(IO1)_2") (pintype "bidirectional"))
    )
    (net (code "20") (name "MOSI") (class "Default")
      (node (ref "D11") (pin "2") (pinfunction "2_2") (pintype "passive"))
      (node (ref "J1") (pin "14") (pinfunction "14_14") (pintype "bidirectional"))
      (node (ref "J4") (pin "P3") (pinfunction "CMD_P3") (pintype "bidirectional"))
      (node (ref "R7") (pin "1") (pinfunction "1_1") (pintype "passive"))
      (node (ref "TP7") (pin "TP") (pinfunction "TP_TP") (pintype "input"))
      (node (ref "U1") (pin "7") (pinfunction "IO7_7") (pintype "bidirectional"))
      (node (ref "U5") (pin "5") (pinfunction "DI(IO0)_5") (pintype "bidirectional"))
    )
    (net (code "21") (name "Net-(CHG_LED-PadC)") (class "Default")
      (node (ref "CHG_LED") (pin "C") (pinfunction "C_C") (pintype "passive"))
      (node (ref "R1_BAT") (pin "1") (pinfunction "1_1") (pintype "passive"))
    )
    (net (code "22") (name "Net-(D2-CATHODE)") (class "Default")
      (node (ref "C1_BAT1") (pin "1") (pinfunction "1_1") (pintype "passive"))
      (node (ref "D2") (pin "1") (pinfunction "CATHODE_1") (pintype "bidirectional"))
      (node (ref "IC4") (pin "1") (pinfunction "VIN_1") (pintype "bidirectional"))
      (node (ref "IC4") (pin "3") (pinfunction "CE_3") (pintype "bidirectional"))
      (node (ref "Q1") (pin "2") (pinfunction "S_2") (pintype "bidirectional"))
    )
    (net (code "23") (name "Net-(D3-A)") (class "Default")
      (node (ref "C4") (pin "1") (pinfunction "1_1") (pintype "passive"))
      (node (ref "D3") (pin "2") (pinfunction "A_2") (pintype "bidirectional"))
      (node (ref "D4") (pin "1") (pinfunction "K_1") (pintype "bidirectional"))
    )
    (net (code "24") (name "Net-(D7-CATHODE)") (class "Default")
      (node (ref "D7") (pin "1") (pinfunction "CATHODE_1") (pintype "bidirectional"))
      (node (ref "R_CAPACITOR") (pin "1") (pinfunction "1_1") (pintype "passive"))
    )
    (net (code "25") (name "Net-(EPD_C1-Pad2)") (class "Default")
      (node (ref "EPD_C1") (pin "2") (pinfunction "2_2") (pintype "passive"))
      (node (ref "J1") (pin "4") (pinfunction "4_4") (pintype "bidirectional"))
    )
    (net (code "26") (name "Net-(EPD_C2-Pad2)") (class "Default")
      (node (ref "EPD_C2") (pin "2") (pinfunction "2_2") (pintype "passive"))
      (node (ref "J1") (pin "5") (pinfunction "5_5") (pintype "bidirectional"))
    )
    (net (code "27") (name "Net-(EPD_C6-Pad2)") (class "Default")
      (node (ref "EPD_C6") (pin "2") (pinfunction "2_2") (pintype "passive"))
      (node (ref "J1") (pin "18") (pinfunction "18_18") (pintype "bidirectional"))
    )
    (net (code "28") (name "Net-(EPD_C7-Pad2)") (class "Default")
      (node (ref "EPD_C7") (pin "2") (pinfunction "2_2") (pintype "passive"))
      (node (ref "J1") (pin "19") (pinfunction "19_19") (pintype "bidirectional"))
    )
    (net (code "29") (name "Net-(EPD_C8-Pad2)") (class "Default")
      (node (ref "EPD_C8") (pin "2") (pinfunction "2_2") (pintype "passive"))
      (node (ref "J1") (pin "20") (pinfunction "20_20") (pintype "bidirectional"))
    )
    (net (code "30") (name "Net-(EPD_C10-Pad2)") (class "Default")
      (node (ref "EPD_C10") (pin "2") (pinfunction "2_2") (pintype "passive"))
      (node (ref "J1") (pin "22") (pinfunction "22_22") (pintype "bidirectional"))
    )
    (net (code "31") (name "Net-(EPD_C12-Pad2)") (class "Default")
      (node (ref "EPD_C12") (pin "2") (pinfunction "2_2") (pintype "passive"))
      (node (ref "J1") (pin "24") (pinfunction "24_24") (pintype "bidirectional"))
    )
    (net (code "32") (name "Net-(IC2-CT)") (class "Default")
      (node (ref "C_DELAY") (pin "1") (pinfunction "1_1") (pintype "passive"))
      (node (ref "IC2") (pin "5") (pinfunction "CT_5") (pintype "bidirectional"))
    )
    (net (code "33") (name "Net-(J2-PadA5)") (class "Default")
      (node (ref "J2") (pin "A5") (pinfunction "A5_A5") (pintype "bidirectional"))
      (node (ref "R2-USB1") (pin "2") (pinfunction "2_2") (pintype "passive"))
    )
    (net (code "34") (name "Net-(J2-PadB5)") (class "Default")
      (node (ref "J2") (pin "B5") (pinfunction "B5_B5") (pintype "bidirectional"))
      (node (ref "R2-USB") (pin "1") (pinfunction "1_1") (pintype "passive"))
    )
    (net (code "35") (name "Net-(U2-PROG)") (class "Default")
      (node (ref "R2_BAT") (pin "2") (pinfunction "2_2") (pintype "passive"))
      (node (ref "U2") (pin "5") (pinfunction "PROG_5") (pintype "input"))
    )
    (net (code "36") (name "Net-(U2-STAT)") (class "Default")
      (node (ref "R1_BAT") (pin "2") (pinfunction "2_2") (pintype "passive"))
      (node (ref "U2") (pin "1") (pinfunction "STAT_1") (pintype "output"))
    )
    (net (code "37") (name "PREVGH") (class "Default")
      (node (ref "D5") (pin "1") (pinfunction "K_1") (pintype "bidirectional"))
      (node (ref "EPD_C9") (pin "2") (pinfunction "2_2") (pintype "passive"))
      (node (ref "J1") (pin "21") (pinfunction "21_21") (pintype "bidirectional"))
    )
    (net (code "38") (name "PREVGL") (class "Default")
      (node (ref "D4") (pin "2") (pinfunction "A_2") (pintype "bidirectional"))
      (node (ref "EPD_C11") (pin "2") (pinfunction "2_2") (pintype "passive"))
      (node (ref "J1") (pin "23") (pinfunction "23_23") (pintype "bidirectional"))
    )
    (net (code "39") (name "RESE") (class "Default")
      (node (ref "J1") (pin "3") (pinfunction "3_3") (pintype "bidirectional"))
      (node (ref "Q3") (pin "2") (pinfunction "S_2") (pintype "bidirectional"))
      (node (ref "R3") (pin "2") (pinfunction "2_2") (pintype "passive"))
    )
    (net (code "40") (name "RESE'") (class "Default")
      (node (ref "R2") (pin "2") (pinfunction "2_2") (pintype "passive"))
      (node (ref "R3") (pin "1") (pinfunction "1_1") (pintype "passive"))
      (node (ref "SJ1") (pin "2") (pinfunction "2_2") (pintype "passive"))
    )
    (net (code "41") (name "RESET") (class "Default")
      (node (ref "C5") (pin "1") (pinfunction "1_1") (pintype "passive"))
      (node (ref "IC2") (pin "1") (pinfunction "VOUT_1") (pintype "bidirectional"))
      (node (ref "RESET_BUTTON") (pin "3") (pinfunction "3_3") (pintype "passive"))
      (node (ref "RESET_BUTTON") (pin "4") (pinfunction "4_4") (pintype "passive"))
      (node (ref "R_RESET") (pin "1") (pinfunction "1_1") (pintype "passive"))
      (node (ref "U1") (pin "3") (pinfunction "EN_3") (pintype "input"))
    )
    (net (code "42") (name "RTC_RST") (class "Default")
      (node (ref "U1") (pin "16") (pinfunction "IO18_16") (pintype "bidirectional"))
      (node (ref "U3") (pin "4") (pinfunction "~{RST}_4") (pintype "input"))
    )
    (net (code "43") (name "RX") (class "Default")
      (node (ref "TP2") (pin "TP") (pinfunction "TP_TP") (pintype "input"))
      (node (ref "U1") (pin "24") (pinfunction "RXD0/GPIO17_24") (pintype "bidirectional"))
    )
    (net (code "44") (name "SCK") (class "Default")
      (node (ref "D10") (pin "2") (pinfunction "2_2") (pintype "passive"))
      (node (ref "J1") (pin "13") (pinfunction "13_13") (pintype "bidirectional"))
      (node (ref "J4") (pin "P5") (pinfunction "CLK_P5") (pintype "bidirectional"))
      (node (ref "R6") (pin "1") (pinfunction "1_1") (pintype "passive"))
      (node (ref "TP8") (pin "TP") (pinfunction "TP_TP") (pintype "input"))
      (node (ref "U1") (pin "6") (pinfunction "IO6_6") (pintype "bidirectional"))
      (node (ref "U5") (pin "6") (pinfunction "CLK_6") (pintype "input"))
    )
    (net (code "45") (name "SCL") (class "Default")
      (node (ref "J3") (pin "4") (pinfunction "4_4") (pintype "passive"))
      (node (ref "R2_PINH") (pin "1") (pinfunction "1_1") (pintype "passive"))
      (node (ref "U1") (pin "20") (pinfunction "IO22_20") (pintype "bidirectional"))
      (node (ref "U3") (pin "16") (pinfunction "SCL_16") (pintype "input"))
      (node (ref "U4") (pin "7") (pinfunction "SCL_7") (pintype "input"))
      (node (ref "U6") (pin "4") (pinfunction "SCK_4") (pintype "input"))
    )
    (net (code "46") (name "SDA") (class "Default")
      (node (ref "J3") (pin "3") (pinfunction "3_3") (pintype "passive"))
      (node (ref "R1_PINH") (pin "1") (pinfunction "1_1") (pintype "passive"))
      (node (ref "U1") (pin "19") (pinfunction "IO21_19") (pintype "bidirectional"))
      (node (ref "U3") (pin "15") (pinfunction "SDA_15") (pintype "bidirectional"))
      (node (ref "U4") (pin "8") (pinfunction "SDA_8") (pintype "bidirectional"))
      (node (ref "U6") (pin "3") (pinfunction "SDI_3") (pintype "bidirectional"))
    )
    (net (code "47") (name "SRC") (class "Default")
      (node (ref "C4") (pin "2") (pinfunction "2_2") (pintype "passive"))
      (node (ref "D5") (pin "2") (pinfunction "A_2") (pintype "bidirectional"))
      (node (ref "L1") (pin "P$2") (pinfunction "2_P$2") (pintype "passive"))
      (node (ref "Q3") (pin "3") (pinfunction "D_3") (pintype "bidirectional"))
    )
    (net (code "48") (name "SS_SD") (class "Default")
      (node (ref "D8") (pin "2") (pinfunction "2_2") (pintype "passive"))
      (node (ref "J4") (pin "P2") (pinfunction "CD/DAT3_P2") (pintype "bidirectional"))
      (node (ref "R10") (pin "1") (pinfunction "1_1") (pintype "passive"))
      (node (ref "U1") (pin "4") (pinfunction "IO4_4") (pintype "bidirectional"))
    )
    (net (code "49") (name "TX") (class "Default")
      (node (ref "TP1") (pin "TP") (pinfunction "TP_TP") (pintype "input"))
      (node (ref "U1") (pin "25") (pinfunction "TXD0/GPIO16_25") (pintype "bidirectional"))
    )
    (net (code "50") (name "USB_D+") (class "Default")
      (node (ref "D1") (pin "4") (pinfunction "I/O2_2_4") (pintype "bidirectional"))
      (node (ref "U1") (pin "14") (pinfunction "IO13_14") (pintype "bidirectional"))
    )
    (net (code "51") (name "USB_D-") (class "Default")
      (node (ref "D1") (pin "6") (pinfunction "I/O1_2_6") (pintype "bidirectional"))
      (node (ref "U1") (pin "13") (pinfunction "IO12_13") (pintype "bidirectional"))
    )
    (net (code "52") (name "VBAT") (class "Default")
      (node (ref "C2_BAT") (pin "1") (pinfunction "1_1") (pintype "passive"))
      (node (ref "Q1") (pin "3") (pinfunction "D_3") (pintype "bidirectional"))
      (node (ref "TP3") (pin "TP") (pinfunction "TP_TP") (pintype "input"))
      (node (ref "U2") (pin "3") (pinfunction "VBAT_3") (pintype "power_in"))
      (node (ref "U4") (pin "2") (pinfunction "CELL_2") (pintype "power_in"))
      (node (ref "U4") (pin "3") (pinfunction "VDD_3") (pintype "power_in"))
    )
    (net (code "53") (name "VBUS") (class "Default")
      (node (ref "C1_BAT") (pin "1") (pinfunction "1_1") (pintype "passive"))
      (node (ref "C4_USB") (pin "1") (pinfunction "1_1") (pintype "passive"))
      (node (ref "C5_USB") (pin "1") (pinfunction "1_1") (pintype "passive"))
      (node (ref "CHG_LED") (pin "A") (pinfunction "A_A") (pintype "passive"))
      (node (ref "D1") (pin "2") (pinfunction "GND_2") (pintype "bidirectional"))
      (node (ref "D2") (pin "2") (pinfunction "ANODE_2") (pintype "bidirectional"))
      (node (ref "PFMF.050.1") (pin "2") (pinfunction "2_2") (pintype "passive"))
      (node (ref "Q1") (pin "1") (pinfunction "G_1") (pintype "bidirectional"))
      (node (ref "R1_PWRUSB") (pin "2") (pinfunction "2_2") (pintype "passive"))
      (node (ref "TP14") (pin "TP") (pinfunction "TP_TP") (pintype "input"))
      (node (ref "U2") (pin "4") (pinfunction "VIN_4") (pintype "power_in"))
    )
    (net (code "54") (name "VRTC") (class "Default")
      (node (ref "C10_SUPERCAP") (pin "1") (pinfunction "1_1") (pintype "passive"))
      (node (ref "C8") (pin "1") (pinfunction "1_1") (pintype "passive"))
      (node (ref "R_CAPACITOR") (pin "2") (pinfunction "2_2") (pintype "passive"))
      (node (ref "U3") (pin "14") (pinfunction "VBAT_14") (pintype "power_in"))
    )
    (net (code "55") (name "VUSB") (class "Default")
      (node (ref "J2") (pin "A4") (pinfunction "A4_A4") (pintype "bidirectional"))
      (node (ref "J2") (pin "A9") (pinfunction "A9_A9") (pintype "bidirectional"))
      (node (ref "J2") (pin "B4") (pinfunction "B4_B4") (pintype "bidirectional"))
      (node (ref "J2") (pin "B9") (pinfunction "B9_B9") (pintype "bidirectional"))
      (node (ref "PFMF.050.1") (pin "1") (pinfunction "1_1") (pintype "passive"))
    )
    (net (code "56") (name "unconnected-(IC2-NC-Pad4)") (class "Default")
      (node (ref "IC2") (pin "4") (pinfunction "NC_4") (pintype "no_connect"))
    )
    (net (code "57") (name "unconnected-(IC4-NC-Pad4)") (class "Default")
      (node (ref "IC4") (pin "4") (pinfunction "NC_4") (pintype "no_connect"))
    )
    (net (code "58") (name "unconnected-(J1-Pad1)") (class "Default")
      (node (ref "J1") (pin "1") (pinfunction "1_1") (pintype "bidirectional"))
    )
    (net (code "59") (name "unconnected-(J1-Pad6)") (class "Default")
      (node (ref "J1") (pin "6") (pinfunction "6_6") (pintype "bidirectional"))
    )
    (net (code "60") (name "unconnected-(J1-Pad7)") (class "Default")
      (node (ref "J1") (pin "7") (pinfunction "7_7") (pintype "bidirectional"))
    )
    (net (code "61") (name "unconnected-(J2-PadA8)") (class "Default")
      (node (ref "J2") (pin "A8") (pinfunction "A8_A8") (pintype "bidirectional"))
    )
    (net (code "62") (name "unconnected-(J2-PadB8)") (class "Default")
      (node (ref "J2") (pin "B8") (pinfunction "B8_B8") (pintype "bidirectional"))
    )
    (net (code "63") (name "unconnected-(J4-DAT1-PadP8)") (class "Default")
      (node (ref "J4") (pin "P8") (pinfunction "DAT1_P8") (pintype "bidirectional"))
    )
    (net (code "64") (name "unconnected-(J4-DAT2-PadP1)") (class "Default")
      (node (ref "J4") (pin "P1") (pinfunction "DAT2_P1") (pintype "bidirectional"))
    )
    (net (code "65") (name "unconnected-(J4-DETECTION_1-PadS1)") (class "Default")
      (node (ref "J4") (pin "S1") (pinfunction "DETECTION_1_S1") (pintype "bidirectional"))
    )
    (net (code "66") (name "unconnected-(J4-DETECTION_2-PadS2)") (class "Default")
      (node (ref "J4") (pin "S2") (pinfunction "DETECTION_2_S2") (pintype "bidirectional"))
    )
    (net (code "67") (name "unconnected-(U1-NC-Pad22)") (class "Default")
      (node (ref "U1") (pin "22") (pinfunction "NC_22") (pintype "no_connect"))
    )
    (net (code "68") (name "unconnected-(U4-~{ALERT}-Pad5)") (class "Default")
      (node (ref "U4") (pin "5") (pinfunction "~{ALERT}_5") (pintype "output"))
    )
  )
)
